# LPY503AL-Breakout-v1_0.net
KiCad netlist of a schematic drawn in EAGLE
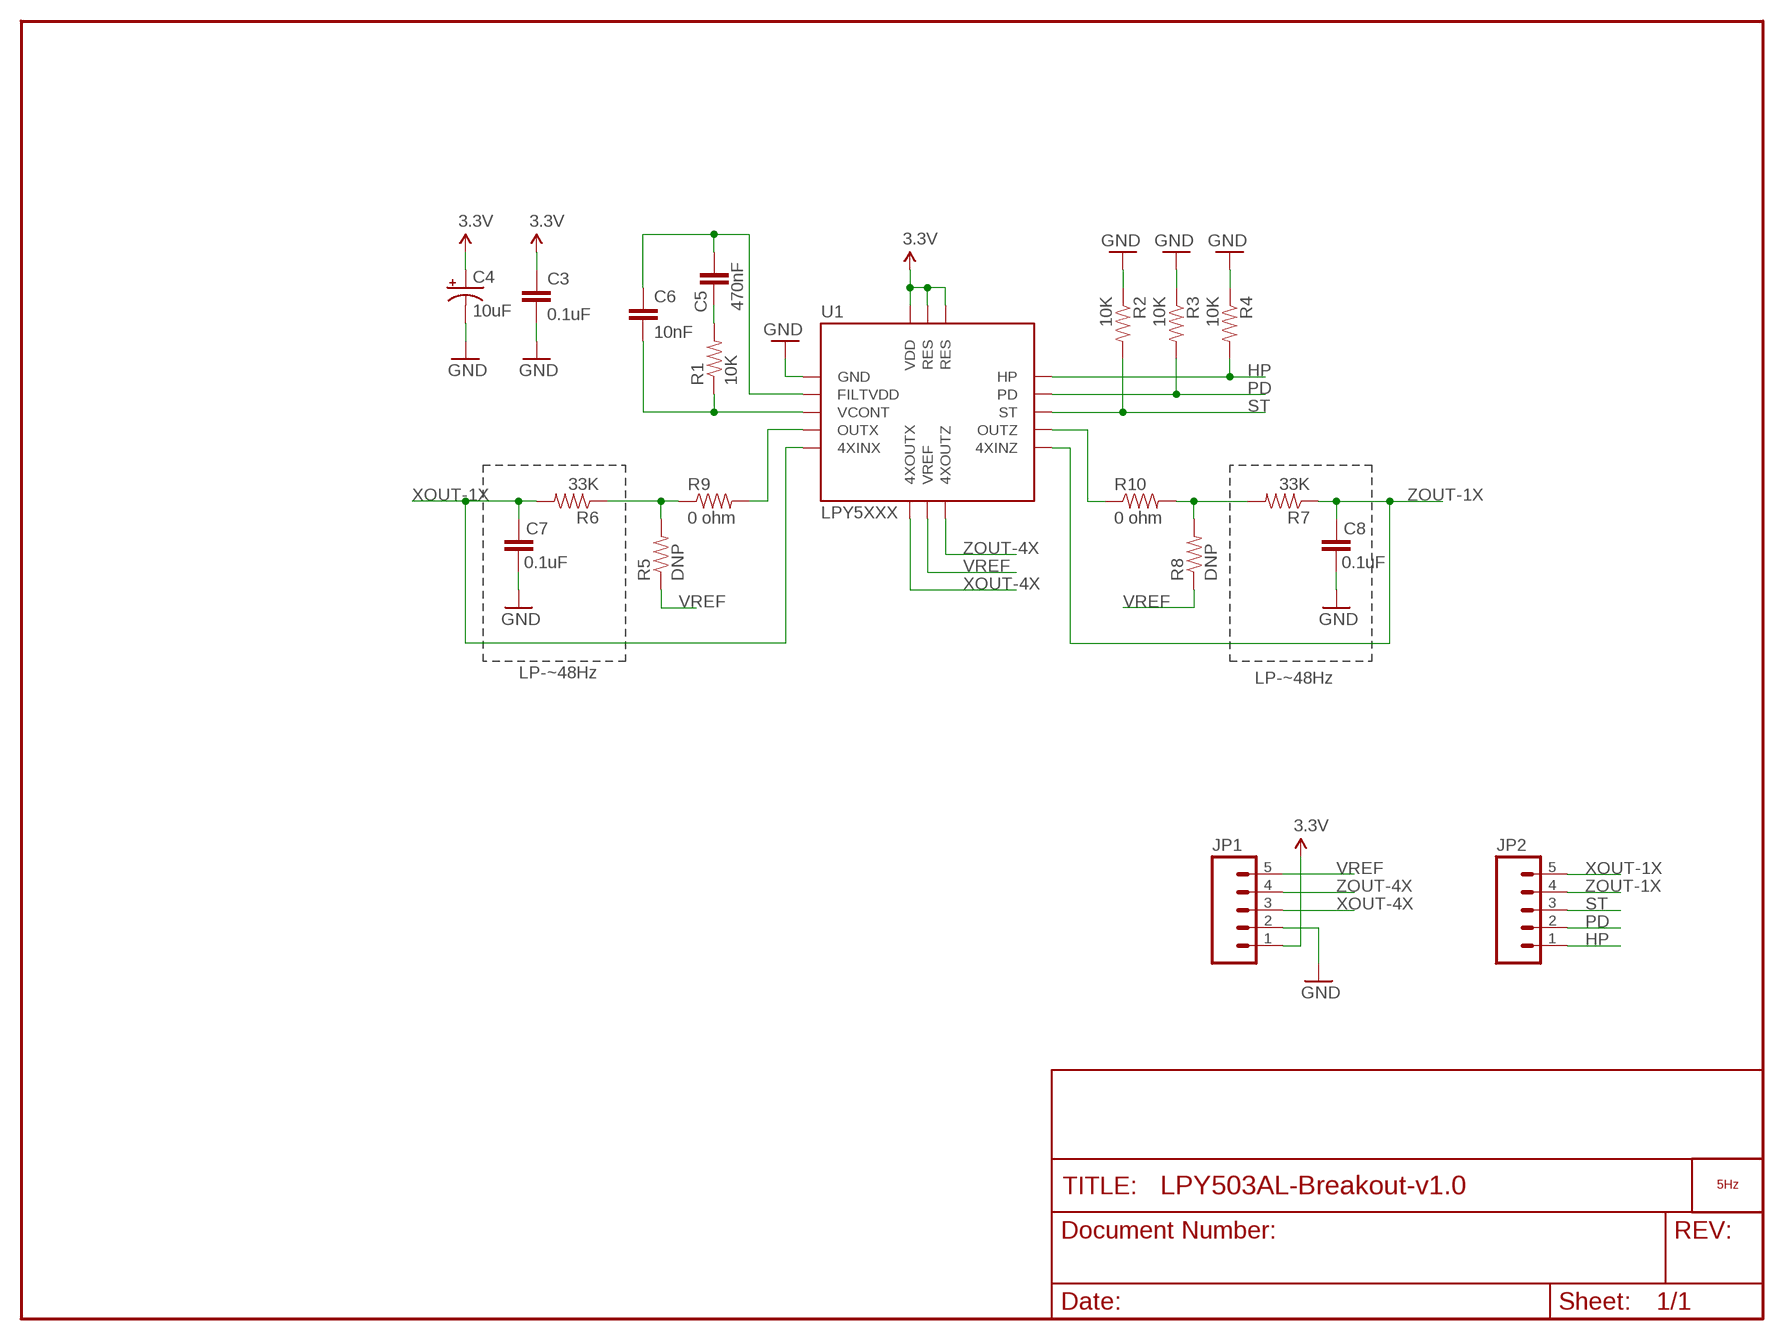
[diagram p0: schematic, sheet 1]

(export (version "E")
  (design (tool "Eeschema 10.0.6"))
  (components
    (comp (ref "C3")
      (value "0.1uF")
      (footprint "eagle-import:0402-CAP")
      (libsource (lib "eagle-import") (part "CAP0402-CAP"))
    )
    (comp (ref "C4")
      (value "10uF")
      (footprint "eagle-import:EIA3216")
      (libsource (lib "eagle-import") (part "CAP_POL1206"))
    )
    (comp (ref "C5")
      (value "470nF")
      (footprint "eagle-import:0402-CAP")
      (libsource (lib "eagle-import") (part "CAP0402-CAP"))
    )
    (comp (ref "C6")
      (value "10nF")
      (footprint "eagle-import:0402-CAP")
      (libsource (lib "eagle-import") (part "CAP0402-CAP"))
    )
    (comp (ref "C7")
      (value "0.1uF")
      (footprint "eagle-import:0402-CAP")
      (libsource (lib "eagle-import") (part "CAP0402-CAP"))
    )
    (comp (ref "C8")
      (value "0.1uF")
      (footprint "eagle-import:0402-CAP")
      (libsource (lib "eagle-import") (part "CAP0402-CAP"))
    )
    (comp (ref "JP1")
      (value "M05PTH")
      (footprint "eagle-import:1X05")
      (libsource (lib "eagle-import") (part "M05PTH"))
    )
    (comp (ref "JP2")
      (value "M05PTH")
      (footprint "eagle-import:1X05")
      (libsource (lib "eagle-import") (part "M05PTH"))
    )
    (comp (ref "LOGO1")
      (value "LOGO_5HZ_MAIN_5MM")
      (footprint "eagle-import:5HZ_LOGO_MAIN_5MM")
      (libsource (lib "eagle-import") (part "LOGO_5HZ_MAIN_5MM"))
    )
    (comp (ref "R1")
      (value "10K")
      (footprint "eagle-import:0402-RES")
      (libsource (lib "eagle-import") (part "RESISTOR0402-RES"))
    )
    (comp (ref "R2")
      (value "10K")
      (footprint "eagle-import:0402-RES")
      (libsource (lib "eagle-import") (part "RESISTOR0402-RES"))
    )
    (comp (ref "R3")
      (value "10K")
      (footprint "eagle-import:0402-RES")
      (libsource (lib "eagle-import") (part "RESISTOR0402-RES"))
    )
    (comp (ref "R4")
      (value "10K")
      (footprint "eagle-import:0402-RES")
      (libsource (lib "eagle-import") (part "RESISTOR0402-RES"))
    )
    (comp (ref "R5")
      (value "DNP")
      (footprint "eagle-import:0402-RES")
      (libsource (lib "eagle-import") (part "RESISTOR0402-RES"))
    )
    (comp (ref "R6")
      (value "33K")
      (footprint "eagle-import:0402-RES")
      (libsource (lib "eagle-import") (part "RESISTOR0402-RES"))
    )
    (comp (ref "R7")
      (value "33K")
      (footprint "eagle-import:0402-RES")
      (libsource (lib "eagle-import") (part "RESISTOR0402-RES"))
    )
    (comp (ref "R8")
      (value "DNP")
      (footprint "eagle-import:0402-RES")
      (libsource (lib "eagle-import") (part "RESISTOR0402-RES"))
    )
    (comp (ref "R9")
      (value "0 ohm")
      (footprint "eagle-import:0402-RES")
      (libsource (lib "eagle-import") (part "RESISTOR0402-RES"))
    )
    (comp (ref "R10")
      (value "0 ohm")
      (footprint "eagle-import:0402-RES")
      (libsource (lib "eagle-import") (part "RESISTOR0402-RES"))
    )
    (comp (ref "U1")
      (value "LPY5XXX")
      (footprint "eagle-import:ST-GYRO")
      (libsource (lib "eagle-import") (part "ST-GYRO-PYSMD"))
    )
  )
  (nets
    (net (code "1") (name "/HP") (class "Default")
      (node (ref "JP2") (pin "1") (pinfunction "1_1") (pintype "passive"))
      (node (ref "R4") (pin "2") (pinfunction "2_2") (pintype "passive"))
      (node (ref "U1") (pin "13") (pinfunction "HP_13") (pintype "bidirectional"))
    )
    (net (code "2") (name "/PD") (class "Default")
      (node (ref "JP2") (pin "2") (pinfunction "2_2") (pintype "passive"))
      (node (ref "R3") (pin "2") (pinfunction "2_2") (pintype "passive"))
      (node (ref "U1") (pin "12") (pinfunction "PD_12") (pintype "bidirectional"))
    )
    (net (code "3") (name "/ST") (class "Default")
      (node (ref "JP2") (pin "3") (pinfunction "3_3") (pintype "passive"))
      (node (ref "R2") (pin "2") (pinfunction "2_2") (pintype "passive"))
      (node (ref "U1") (pin "11") (pinfunction "ST_11") (pintype "bidirectional"))
    )
    (net (code "4") (name "/VREF") (class "Default")
      (node (ref "JP1") (pin "5") (pinfunction "5_5") (pintype "passive"))
      (node (ref "R5") (pin "1") (pinfunction "1_1") (pintype "passive"))
      (node (ref "R8") (pin "1") (pinfunction "1_1") (pintype "passive"))
      (node (ref "U1") (pin "7") (pinfunction "VREF_7") (pintype "bidirectional"))
    )
    (net (code "5") (name "/XOUT-1X") (class "Default")
      (node (ref "C7") (pin "2") (pinfunction "2_2") (pintype "passive"))
      (node (ref "JP2") (pin "5") (pinfunction "5_5") (pintype "passive"))
      (node (ref "R6") (pin "2") (pinfunction "2_2") (pintype "passive"))
      (node (ref "U1") (pin "5") (pinfunction "4XINX_5") (pintype "bidirectional"))
    )
    (net (code "6") (name "/XOUT-4X") (class "Default")
      (node (ref "JP1") (pin "3") (pinfunction "3_3") (pintype "passive"))
      (node (ref "U1") (pin "6") (pinfunction "4XOUTX_6") (pintype "bidirectional"))
    )
    (net (code "7") (name "/ZOUT-1X") (class "Default")
      (node (ref "C8") (pin "2") (pinfunction "2_2") (pintype "passive"))
      (node (ref "JP2") (pin "4") (pinfunction "4_4") (pintype "passive"))
      (node (ref "R7") (pin "1") (pinfunction "1_1") (pintype "passive"))
      (node (ref "U1") (pin "9") (pinfunction "4XINZ_9") (pintype "bidirectional"))
    )
    (net (code "8") (name "/ZOUT-4X") (class "Default")
      (node (ref "JP1") (pin "4") (pinfunction "4_4") (pintype "passive"))
      (node (ref "U1") (pin "8") (pinfunction "4XOUTZ_8") (pintype "bidirectional"))
    )
    (net (code "9") (name "3.3V") (class "Default")
      (node (ref "C3") (pin "1") (pinfunction "1_1") (pintype "passive"))
      (node (ref "C4") (pin "A") (pinfunction "+_A") (pintype "passive"))
      (node (ref "JP1") (pin "1") (pinfunction "1_1") (pintype "passive"))
      (node (ref "U1") (pin "14") (pinfunction "RES_14") (pintype "bidirectional"))
      (node (ref "U1") (pin "15") (pinfunction "RES_15") (pintype "bidirectional"))
      (node (ref "U1") (pin "16") (pinfunction "VDD_16") (pintype "bidirectional"))
    )
    (net (code "10") (name "GND") (class "Default")
      (node (ref "C3") (pin "2") (pinfunction "2_2") (pintype "passive"))
      (node (ref "C4") (pin "C") (pinfunction "-_C") (pintype "passive"))
      (node (ref "C7") (pin "1") (pinfunction "1_1") (pintype "passive"))
      (node (ref "C8") (pin "1") (pinfunction "1_1") (pintype "passive"))
      (node (ref "JP1") (pin "2") (pinfunction "2_2") (pintype "passive"))
      (node (ref "R2") (pin "1") (pinfunction "1_1") (pintype "passive"))
      (node (ref "R3") (pin "1") (pinfunction "1_1") (pintype "passive"))
      (node (ref "R4") (pin "1") (pinfunction "1_1") (pintype "passive"))
      (node (ref "U1") (pin "1") (pinfunction "GND_1") (pintype "bidirectional"))
    )
    (net (code "11") (name "Net-(C5-Pad2)") (class "Default")
      (node (ref "C5") (pin "2") (pinfunction "2_2") (pintype "passive"))
      (node (ref "R1") (pin "2") (pinfunction "2_2") (pintype "passive"))
    )
    (net (code "12") (name "Net-(R5-Pad2)") (class "Default")
      (node (ref "R5") (pin "2") (pinfunction "2_2") (pintype "passive"))
      (node (ref "R6") (pin "1") (pinfunction "1_1") (pintype "passive"))
      (node (ref "R9") (pin "1") (pinfunction "1_1") (pintype "passive"))
    )
    (net (code "13") (name "Net-(R10-Pad2)") (class "Default")
      (node (ref "R10") (pin "2") (pinfunction "2_2") (pintype "passive"))
      (node (ref "R7") (pin "2") (pinfunction "2_2") (pintype "passive"))
      (node (ref "R8") (pin "2") (pinfunction "2_2") (pintype "passive"))
    )
    (net (code "14") (name "Net-(U1-FILTVDD)") (class "Default")
      (node (ref "C5") (pin "1") (pinfunction "1_1") (pintype "passive"))
      (node (ref "C6") (pin "1") (pinfunction "1_1") (pintype "passive"))
      (node (ref "U1") (pin "2") (pinfunction "FILTVDD_2") (pintype "bidirectional"))
    )
    (net (code "15") (name "Net-(U1-OUTX)") (class "Default")
      (node (ref "R9") (pin "2") (pinfunction "2_2") (pintype "passive"))
      (node (ref "U1") (pin "4") (pinfunction "OUTX_4") (pintype "bidirectional"))
    )
    (net (code "16") (name "Net-(U1-OUTZ)") (class "Default")
      (node (ref "R10") (pin "1") (pinfunction "1_1") (pintype "passive"))
      (node (ref "U1") (pin "10") (pinfunction "OUTZ_10") (pintype "bidirectional"))
    )
    (net (code "17") (name "Net-(U1-VCONT)") (class "Default")
      (node (ref "C6") (pin "2") (pinfunction "2_2") (pintype "passive"))
      (node (ref "R1") (pin "1") (pinfunction "1_1") (pintype "passive"))
      (node (ref "U1") (pin "3") (pinfunction "VCONT_3") (pintype "bidirectional"))
    )
  )
)
